# LED.net
KiCad netlist of a schematic drawn in Altium Designer
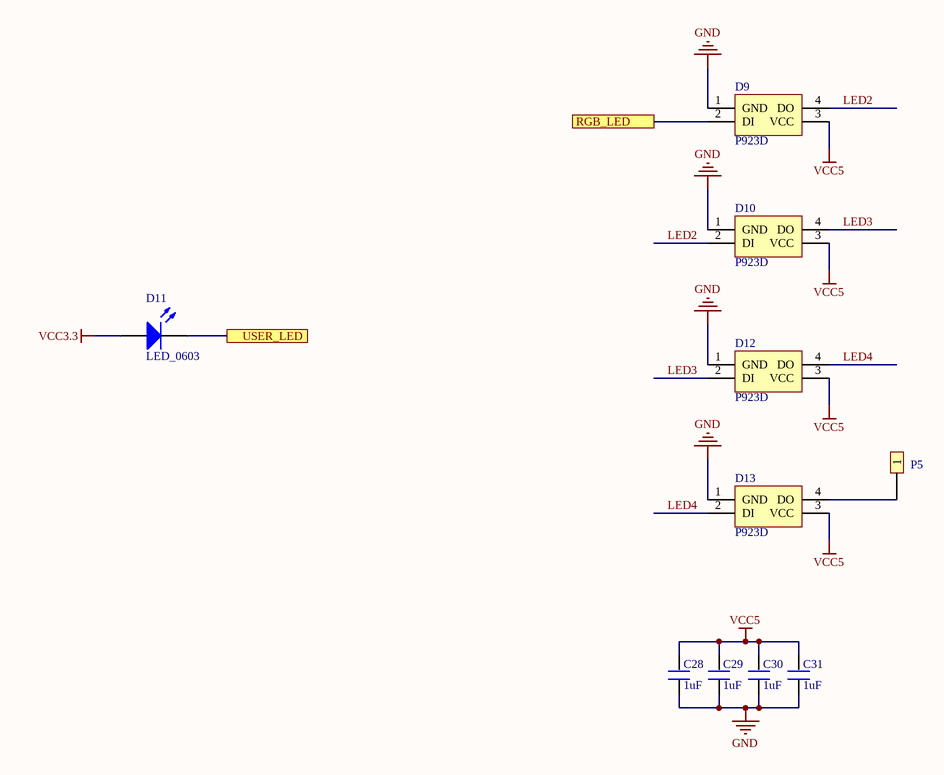
[diagram p0: LED.SchDoc]

(export (version "E")
  (design (tool "Eeschema 10.0.6"))
  (components
    (comp (ref "C28") (value "1uF") (footprint "0603P") (libsource (lib "Explorer STM32F407封装库") (part "C")))
    (comp (ref "C29") (value "1uF") (footprint "0603P") (libsource (lib "Explorer STM32F407封装库") (part "C")))
    (comp (ref "C30") (value "1uF") (footprint "0603P") (libsource (lib "Explorer STM32F407封装库") (part "C")))
    (comp (ref "C31") (value "1uF") (footprint "0603P") (libsource (lib "Explorer STM32F407封装库") (part "C")))
    (comp (ref "D9")
      (value "P923D")
      (footprint "RGB_LED_5050")
      (fields (field (name "PUBLISHER") "mazhongwei"))
      (libsource (lib "RoboFly") (part "P923D"))
    )
    (comp (ref "D10")
      (value "P923D")
      (footprint "RGB_LED_5050")
      (fields (field (name "PUBLISHER") "mazhongwei"))
      (libsource (lib "RoboFly") (part "P923D"))
    )
    (comp (ref "D11")
      (value "LED_0603")
      (footprint "LED-0603")
      (description "发光二极管")
      (fields (field (name "PUBLISHER") "Altium Limited"))
      (libsource (lib "RoboFly") (part "LED 0603"))
    )
    (comp (ref "D12")
      (value "P923D")
      (footprint "RGB_LED_5050")
      (fields (field (name "PUBLISHER") "mazhongwei"))
      (libsource (lib "RoboFly") (part "P923D"))
    )
    (comp (ref "D13")
      (value "P923D")
      (footprint "RGB_LED_5050")
      (fields (field (name "PUBLISHER") "mazhongwei"))
      (libsource (lib "RoboFly") (part "P923D"))
    )
    (comp (ref "P5")
      (value "Header 1")
      (footprint "HEADER1")
      (fields (field (name "PUBLISHER") "Altium Limited"))
      (libsource (lib "RoboFly") (part "Header 1"))
    )
  )
  (nets
    (net (code "1") (name "/LED2") (class "Default")
      (node (ref "D10") (pin "2") (pinfunction "DI_2") (pintype "passive"))
      (node (ref "D9") (pin "4") (pinfunction "DO_4") (pintype "passive"))
    )
    (net (code "2") (name "/LED3") (class "Default")
      (node (ref "D10") (pin "4") (pinfunction "DO_4") (pintype "passive"))
      (node (ref "D12") (pin "2") (pinfunction "DI_2") (pintype "passive"))
    )
    (net (code "3") (name "/LED4") (class "Default")
      (node (ref "D12") (pin "4") (pinfunction "DO_4") (pintype "passive"))
      (node (ref "D13") (pin "2") (pinfunction "DI_2") (pintype "passive"))
    )
    (net (code "4") (name "/RGB_LED") (class "Default")
      (node (ref "D9") (pin "2") (pinfunction "DI_2") (pintype "passive"))
    )
    (net (code "5") (name "/USER_LED") (class "Default")
      (node (ref "D11") (pin "2") (pinfunction "2_2") (pintype "passive"))
    )
    (net (code "6") (name "GND") (class "Default")
      (node (ref "C28") (pin "1") (pintype "passive"))
      (node (ref "C29") (pin "1") (pintype "passive"))
      (node (ref "C30") (pin "1") (pintype "passive"))
      (node (ref "C31") (pin "1") (pintype "passive"))
      (node (ref "D10") (pin "1") (pinfunction "GND_1") (pintype "passive"))
      (node (ref "D12") (pin "1") (pinfunction "GND_1") (pintype "passive"))
      (node (ref "D13") (pin "1") (pinfunction "GND_1") (pintype "passive"))
      (node (ref "D9") (pin "1") (pinfunction "GND_1") (pintype "passive"))
    )
    (net (code "7") (name "Net-(D13-DO)") (class "Default")
      (node (ref "D13") (pin "4") (pinfunction "DO_4") (pintype "passive"))
      (node (ref "P5") (pin "1") (pinfunction "1_1") (pintype "passive"))
    )
    (net (code "8") (name "VCC3.3") (class "Default")
      (node (ref "D11") (pin "1") (pinfunction "1_1") (pintype "passive"))
    )
    (net (code "9") (name "VCC5") (class "Default")
      (node (ref "C28") (pin "2") (pintype "passive"))
      (node (ref "C29") (pin "2") (pintype "passive"))
      (node (ref "C30") (pin "2") (pintype "passive"))
      (node (ref "C31") (pin "2") (pintype "passive"))
      (node (ref "D10") (pin "3") (pinfunction "VCC_3") (pintype "passive"))
      (node (ref "D12") (pin "3") (pinfunction "VCC_3") (pintype "passive"))
      (node (ref "D13") (pin "3") (pinfunction "VCC_3") (pintype "passive"))
      (node (ref "D9") (pin "3") (pinfunction "VCC_3") (pintype "passive"))
    )
  )
)
